# design_sch.net
KiCad netlist of a schematic drawn in EasyEDA
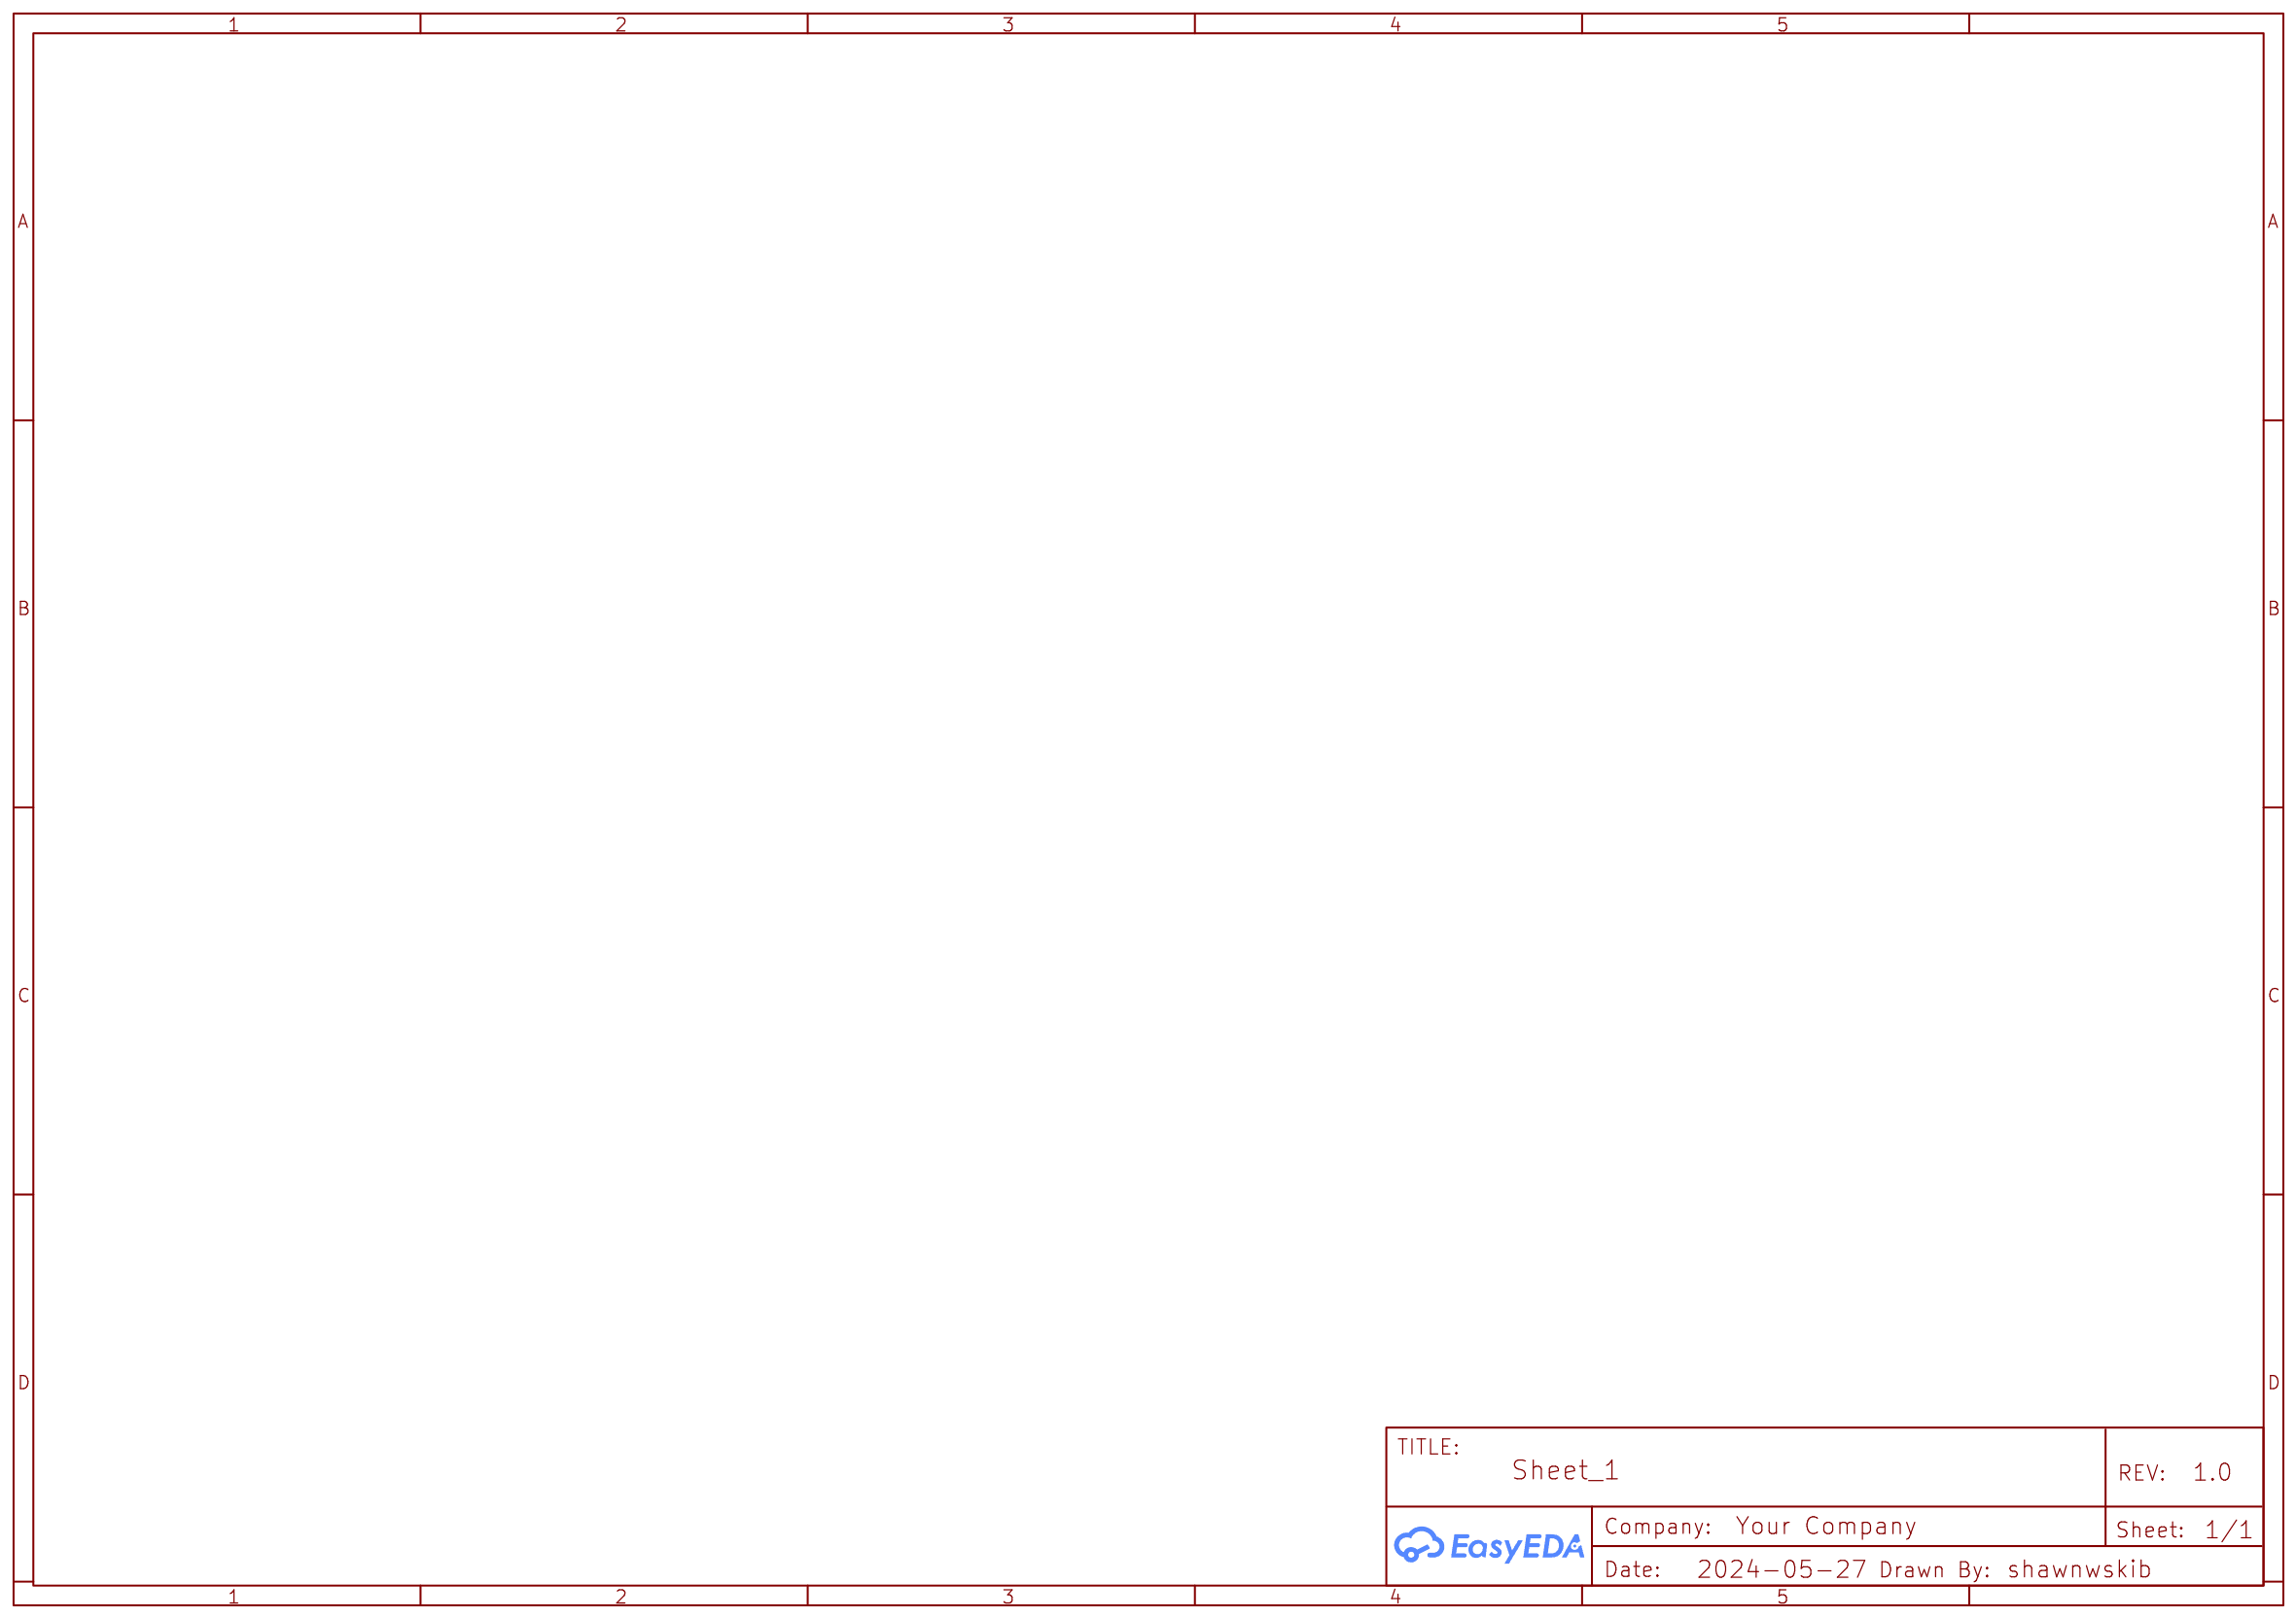
[diagram p0: Sheet_1]
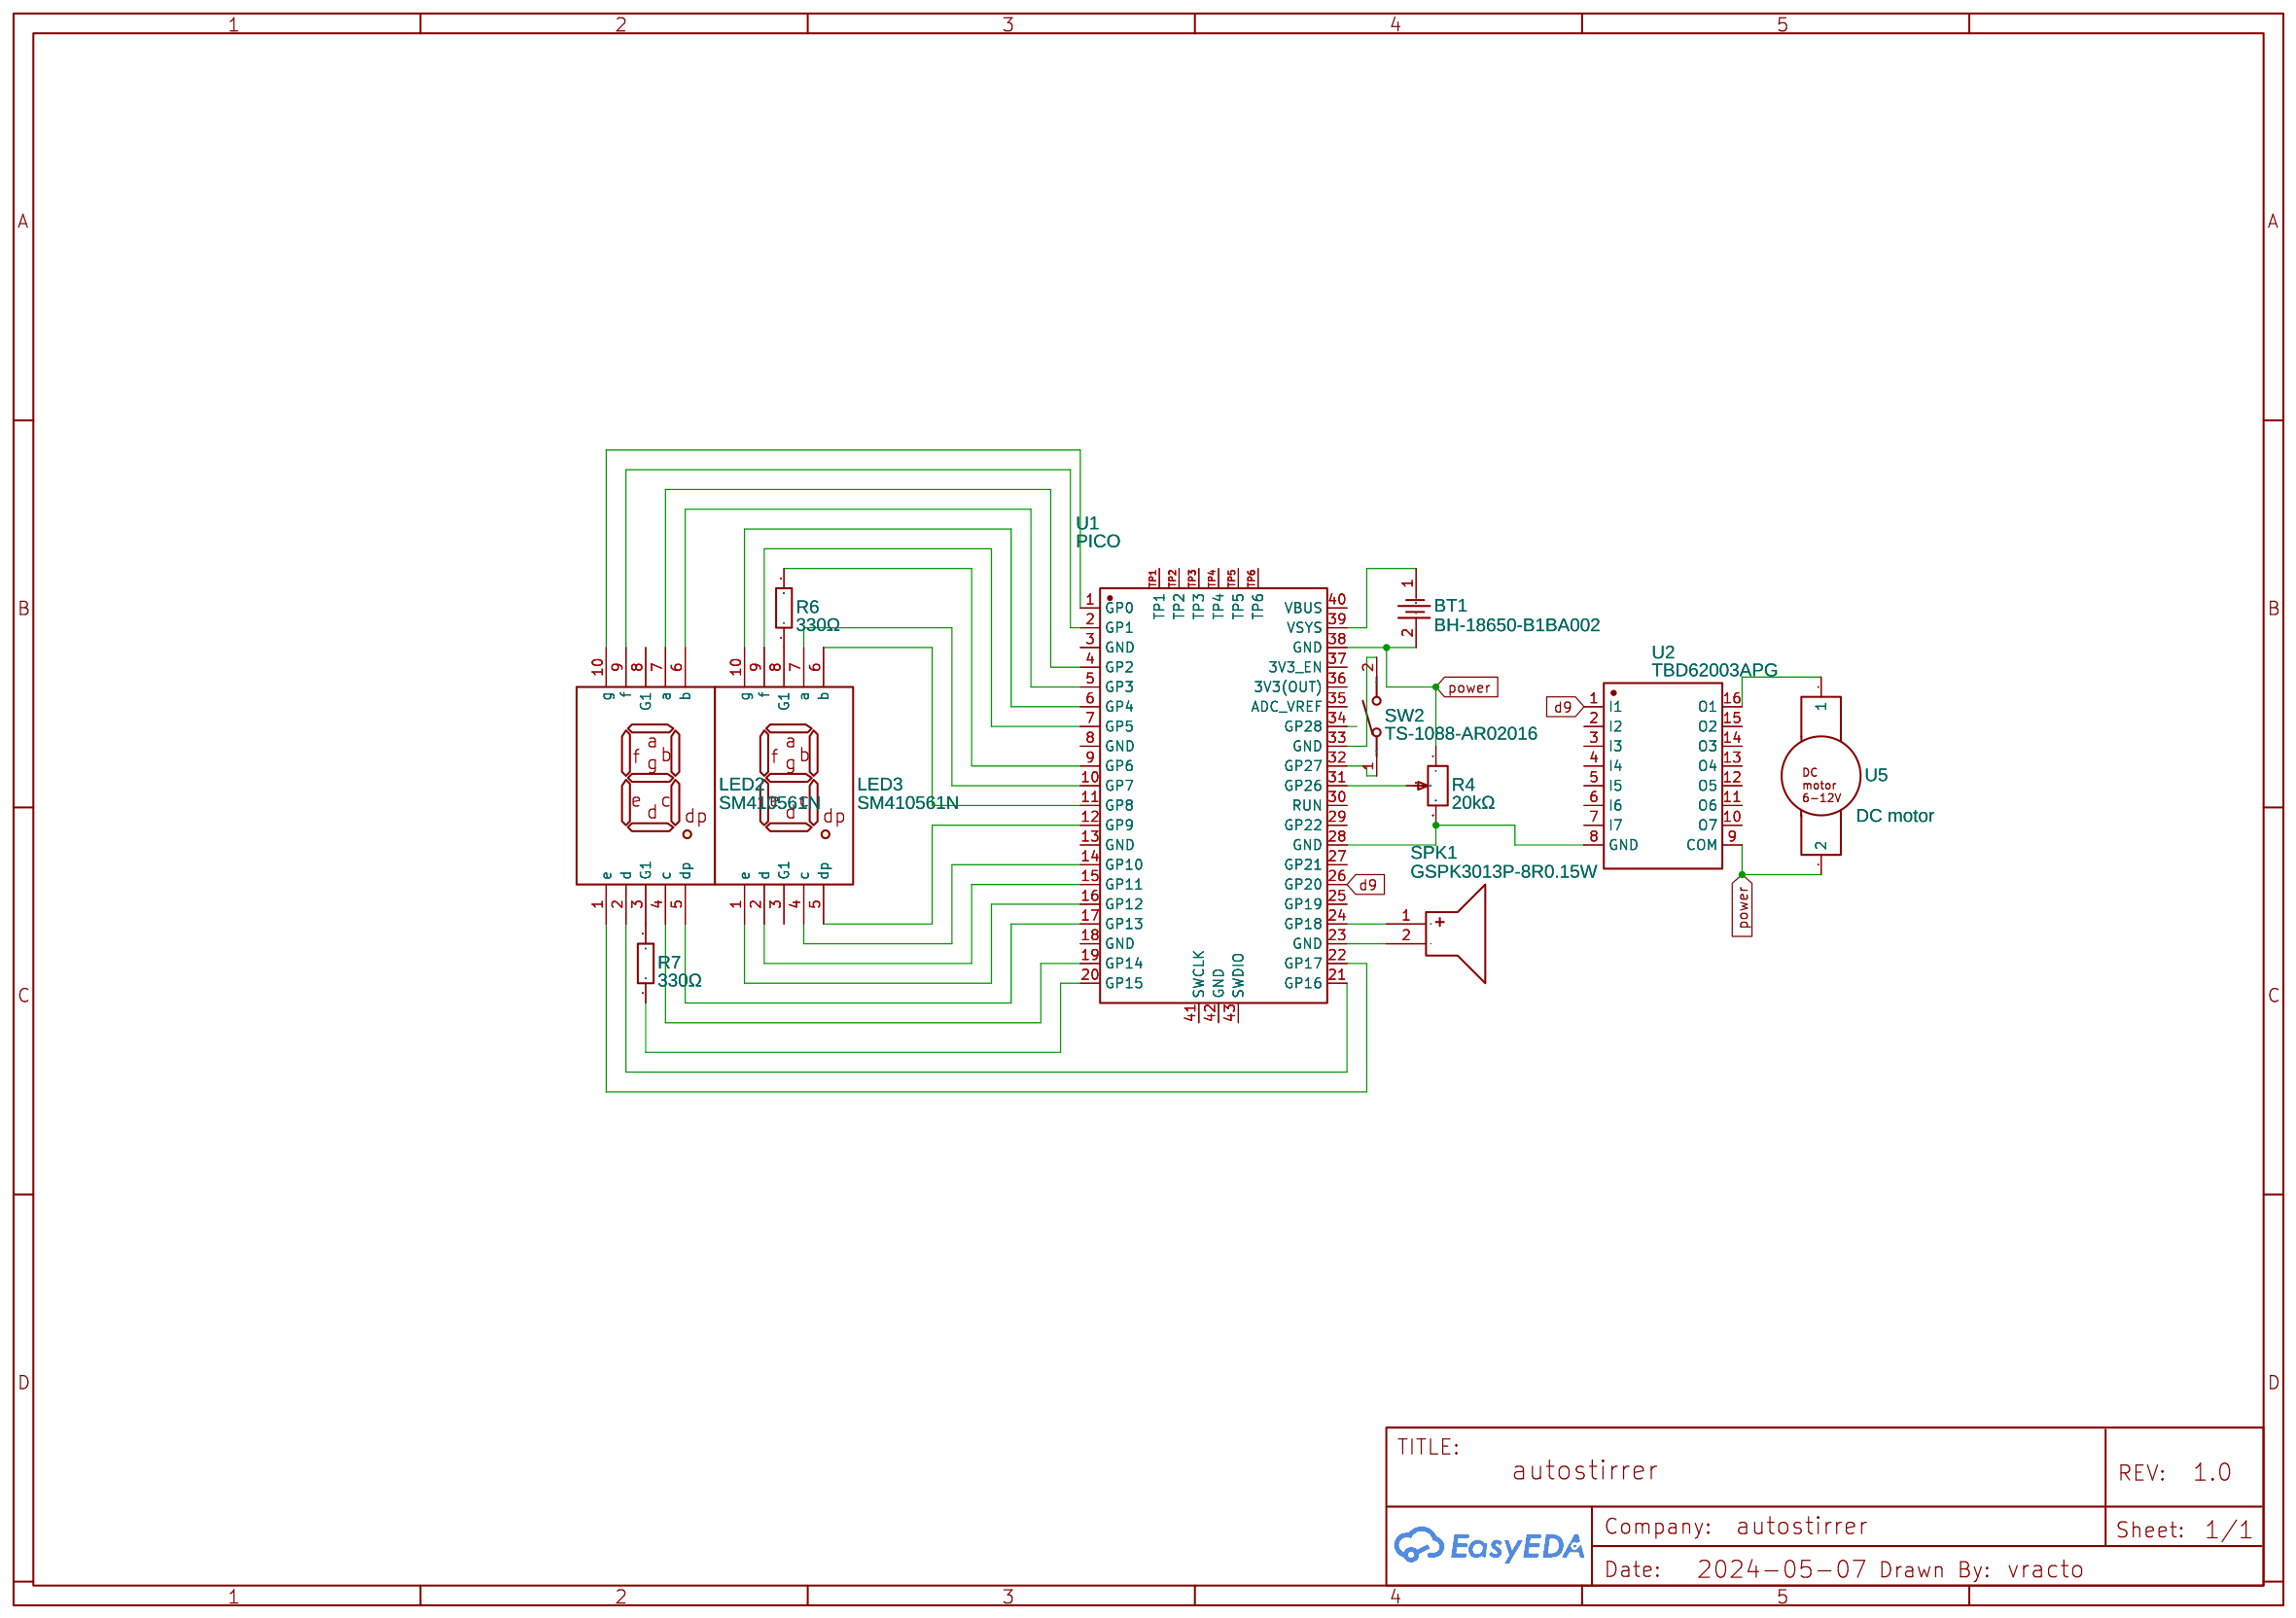
[diagram p1: v1.0.2]

(export (version "E")
  (design (tool "Eeschema 10.0.6"))
  (components
    (comp (ref "BT1")
      (value "BH-18650-B1BA002")
      (fields (field (name "Manufacturer") "MYOUNG(美阳)"))
      (libsource (lib "") (part "BH-18650-B1BA002"))
    )
    (comp (ref "LED2")
      (value "SM410561N")
      (fields (field (name "Manufacturer") "ARKLED(方舟)"))
      (libsource (lib "") (part "SM410561N"))
    )
    (comp (ref "LED3")
      (value "SM410561N")
      (fields (field (name "Manufacturer") "ARKLED(方舟)"))
      (libsource (lib "") (part "SM410561N"))
    )
    (comp (ref "R4")
      (value "20kΩ")
      (fields (field (name "Manufacturer Part") "3296W-1-203LF") (field (name "Manufacturer") "BOURNS"))
      (libsource (lib "") (part "3296W-1-203LF"))
    )
    (comp (ref "R6")
      (value "330Ω")
      (fields (field (name "Manufacturer Part") "MFR-25FTE52-330R") (field (name "Manufacturer") "YAGEO(国巨)"))
      (libsource (lib "") (part "MFR-25FTE52-330R"))
    )
    (comp (ref "R7")
      (value "330Ω")
      (fields (field (name "Manufacturer Part") "MFR-25FTE52-330R") (field (name "Manufacturer") "YAGEO(国巨)"))
      (libsource (lib "") (part "MFR-25FTE52-330R"))
    )
    (comp (ref "SPK1")
      (value "GSPK3013P-8R0.15W")
      (fields (field (name "Manufacturer") "INGHAi(赢海)"))
      (libsource (lib "") (part "GSPK3013P-8R0.15W"))
    )
    (comp (ref "SW2")
      (value "TS-1088-AR02016")
      (fields (field (name "Manufacturer") "XUNPU(讯普)"))
      (libsource (lib "") (part "TS-1088-AR02016"))
    )
    (comp (ref "U1")
      (value "PICO")
      (fields (field (name "Manufacturer") "Raspberry Pi(树莓派)"))
      (libsource (lib "") (part "PICO"))
    )
    (comp (ref "U2")
      (value "TBD62003APG")
      (fields
        (field (name "Manufacturer Part") "TBD62003APG(Z,HZ)")
        (field (name "Manufacturer") "TOSHIBA(东芝)")
      )
      (libsource (lib "") (part "TBD62003APG"))
    )
    (comp (ref "U5")
      (value "DC motor")
      (fields (field (name "Manufacturer Part") "?"))
      (libsource (lib "") (part "Unknown_915_-420"))
    )
  )
  (nets
    (net (code "1") (name "Net-(LED2-G1-Pad3)") (class "Default")
      (node (ref "LED2") (pin "3") (pinfunction "G1_3") (pintype "input"))
      (node (ref "R7") (pin "2") (pinfunction "2_2") (pintype "input"))
    )
    (net (code "2") (name "Net-(LED2-a)") (class "Default")
      (node (ref "LED2") (pin "7") (pinfunction "a_7") (pintype "input"))
      (node (ref "U1") (pin "4") (pinfunction "GP2_4") (pintype "unspecified"))
    )
    (net (code "3") (name "Net-(LED2-b)") (class "Default")
      (node (ref "LED2") (pin "6") (pinfunction "b_6") (pintype "input"))
      (node (ref "U1") (pin "5") (pinfunction "GP3_5") (pintype "unspecified"))
    )
    (net (code "4") (name "Net-(LED2-c)") (class "Default")
      (node (ref "LED2") (pin "4") (pinfunction "c_4") (pintype "input"))
      (node (ref "U1") (pin "19") (pinfunction "GP14_19") (pintype "unspecified"))
    )
    (net (code "5") (name "Net-(LED2-d)") (class "Default")
      (node (ref "LED2") (pin "2") (pinfunction "d_2") (pintype "input"))
      (node (ref "U1") (pin "21") (pinfunction "GP16_21") (pintype "unspecified"))
    )
    (net (code "6") (name "Net-(LED2-dp)") (class "Default")
      (node (ref "LED2") (pin "5") (pinfunction "dp_5") (pintype "input"))
      (node (ref "U1") (pin "17") (pinfunction "GP13_17") (pintype "unspecified"))
    )
    (net (code "7") (name "Net-(LED2-e)") (class "Default")
      (node (ref "LED2") (pin "1") (pinfunction "e_1") (pintype "input"))
      (node (ref "U1") (pin "22") (pinfunction "GP17_22") (pintype "unspecified"))
    )
    (net (code "8") (name "Net-(LED2-f)") (class "Default")
      (node (ref "LED2") (pin "9") (pinfunction "f_9") (pintype "input"))
      (node (ref "U1") (pin "2") (pinfunction "GP1_2") (pintype "unspecified"))
    )
    (net (code "9") (name "Net-(LED2-g)") (class "Default")
      (node (ref "LED2") (pin "10") (pinfunction "g_10") (pintype "input"))
      (node (ref "U1") (pin "1") (pinfunction "GP0_1") (pintype "unspecified"))
    )
    (net (code "10") (name "Net-(LED3-G1-Pad8)") (class "Default")
      (node (ref "LED3") (pin "8") (pinfunction "G1_8") (pintype "input"))
      (node (ref "R6") (pin "1") (pinfunction "1_1") (pintype "input"))
    )
    (net (code "11") (name "Net-(LED3-a)") (class "Default")
      (node (ref "LED3") (pin "7") (pinfunction "a_7") (pintype "input"))
      (node (ref "U1") (pin "10") (pinfunction "GP7_10") (pintype "unspecified"))
    )
    (net (code "12") (name "Net-(LED3-b)") (class "Default")
      (node (ref "LED3") (pin "6") (pinfunction "b_6") (pintype "input"))
      (node (ref "U1") (pin "11") (pinfunction "GP8_11") (pintype "unspecified"))
    )
    (net (code "13") (name "Net-(LED3-c)") (class "Default")
      (node (ref "LED3") (pin "4") (pinfunction "c_4") (pintype "input"))
      (node (ref "U1") (pin "14") (pinfunction "GP10_14") (pintype "unspecified"))
    )
    (net (code "14") (name "Net-(LED3-d)") (class "Default")
      (node (ref "LED3") (pin "2") (pinfunction "d_2") (pintype "input"))
      (node (ref "U1") (pin "15") (pinfunction "GP11_15") (pintype "unspecified"))
    )
    (net (code "15") (name "Net-(LED3-dp)") (class "Default")
      (node (ref "LED3") (pin "5") (pinfunction "dp_5") (pintype "input"))
      (node (ref "U1") (pin "12") (pinfunction "GP9_12") (pintype "unspecified"))
    )
    (net (code "16") (name "Net-(LED3-e)") (class "Default")
      (node (ref "LED3") (pin "1") (pinfunction "e_1") (pintype "input"))
      (node (ref "U1") (pin "16") (pinfunction "GP12_16") (pintype "unspecified"))
    )
    (net (code "17") (name "Net-(LED3-f)") (class "Default")
      (node (ref "LED3") (pin "9") (pinfunction "f_9") (pintype "input"))
      (node (ref "U1") (pin "7") (pinfunction "GP5_7") (pintype "unspecified"))
    )
    (net (code "18") (name "Net-(LED3-g)") (class "Default")
      (node (ref "LED3") (pin "10") (pinfunction "g_10") (pintype "input"))
      (node (ref "U1") (pin "6") (pinfunction "GP4_6") (pintype "unspecified"))
    )
    (net (code "19") (name "Net-(SPK1-+)") (class "Default")
      (node (ref "SPK1") (pin "1") (pinfunction "+_1") (pintype "unspecified"))
      (node (ref "U1") (pin "24") (pinfunction "GP18_24") (pintype "unspecified"))
    )
    (net (code "20") (name "Net-(SPK1--)") (class "Default")
      (node (ref "SPK1") (pin "2") (pinfunction "-_2") (pintype "unspecified"))
      (node (ref "U1") (pin "23") (pinfunction "GND_23") (pintype "unspecified"))
    )
    (net (code "21") (name "Net-(SW2-Pad2)") (class "Default")
      (node (ref "SW2") (pin "2") (pinfunction "2_2") (pintype "unspecified"))
      (node (ref "U1") (pin "33") (pinfunction "GND_33") (pintype "unspecified"))
    )
    (net (code "22") (name "Net-(U1-GP6)") (class "Default")
      (node (ref "R6") (pin "2") (pinfunction "2_2") (pintype "input"))
      (node (ref "U1") (pin "9") (pinfunction "GP6_9") (pintype "unspecified"))
    )
    (net (code "23") (name "Net-(U1-GP15)") (class "Default")
      (node (ref "R7") (pin "1") (pinfunction "1_1") (pintype "input"))
      (node (ref "U1") (pin "20") (pinfunction "GP15_20") (pintype "unspecified"))
    )
    (net (code "24") (name "Net-(U1-GP26)") (class "Default")
      (node (ref "R4") (pin "2") (pinfunction "2_2") (pintype "input"))
      (node (ref "U1") (pin "31") (pinfunction "GP26_31") (pintype "unspecified"))
    )
    (net (code "25") (name "Net-(U1-GP27)") (class "Default")
      (node (ref "SW2") (pin "1") (pinfunction "1_1") (pintype "unspecified"))
      (node (ref "U1") (pin "32") (pinfunction "GP27_32") (pintype "unspecified"))
    )
    (net (code "26") (name "Net-(U1-VSYS)") (class "Default")
      (node (ref "BT1") (pin "1") (pinfunction "1_1") (pintype "input"))
      (node (ref "U1") (pin "39") (pinfunction "VSYS_39") (pintype "unspecified"))
    )
    (net (code "27") (name "Net-(U2-GND)") (class "Default")
      (node (ref "R4") (pin "3") (pinfunction "3_3") (pintype "input"))
      (node (ref "U1") (pin "28") (pinfunction "GND_28") (pintype "unspecified"))
      (node (ref "U2") (pin "8") (pinfunction "GND_8") (pintype "unspecified"))
    )
    (net (code "28") (name "Net-(U2-O1)") (class "Default")
      (node (ref "U2") (pin "16") (pinfunction "O1_16") (pintype "unspecified"))
      (node (ref "U5") (pin "1") (pinfunction "1_1") (pintype "unspecified"))
    )
    (net (code "29") (name "d9") (class "Default")
      (node (ref "U1") (pin "26") (pinfunction "GP20_26") (pintype "unspecified"))
      (node (ref "U2") (pin "1") (pinfunction "I1_1") (pintype "unspecified"))
    )
    (net (code "30") (name "power") (class "Default")
      (node (ref "BT1") (pin "2") (pinfunction "2_2") (pintype "input"))
      (node (ref "R4") (pin "1") (pinfunction "1_1") (pintype "input"))
      (node (ref "U1") (pin "38") (pinfunction "GND_38") (pintype "unspecified"))
      (node (ref "U2") (pin "9") (pinfunction "COM_9") (pintype "unspecified"))
      (node (ref "U5") (pin "2") (pinfunction "2_2") (pintype "unspecified"))
    )
    (net (code "31") (name "unconnected-(LED2-G1-Pad8)") (class "Default")
      (node (ref "LED2") (pin "8") (pinfunction "G1_8") (pintype "input"))
    )
    (net (code "32") (name "unconnected-(LED3-G1-Pad3)") (class "Default")
      (node (ref "LED3") (pin "3") (pinfunction "G1_3") (pintype "input"))
    )
    (net (code "33") (name "unconnected-(U1-3V3(OUT)-Pad36)") (class "Default")
      (node (ref "U1") (pin "36") (pinfunction "3V3(OUT)_36") (pintype "unspecified"))
    )
    (net (code "34") (name "unconnected-(U1-3V3_EN-Pad37)") (class "Default")
      (node (ref "U1") (pin "37") (pinfunction "3V3_EN_37") (pintype "unspecified"))
    )
    (net (code "35") (name "unconnected-(U1-ADC_VREF-Pad35)") (class "Default")
      (node (ref "U1") (pin "35") (pinfunction "ADC_VREF_35") (pintype "unspecified"))
    )
    (net (code "36") (name "unconnected-(U1-GND-Pad3)") (class "Default")
      (node (ref "U1") (pin "3") (pinfunction "GND_3") (pintype "unspecified"))
    )
    (net (code "37") (name "unconnected-(U1-GND-Pad8)") (class "Default")
      (node (ref "U1") (pin "8") (pinfunction "GND_8") (pintype "unspecified"))
    )
    (net (code "38") (name "unconnected-(U1-GND-Pad13)") (class "Default")
      (node (ref "U1") (pin "13") (pinfunction "GND_13") (pintype "unspecified"))
    )
    (net (code "39") (name "unconnected-(U1-GND-Pad18)") (class "Default")
      (node (ref "U1") (pin "18") (pinfunction "GND_18") (pintype "unspecified"))
    )
    (net (code "40") (name "unconnected-(U1-GND-Pad42)") (class "Default")
      (node (ref "U1") (pin "42") (pinfunction "GND_42") (pintype "unspecified"))
    )
    (net (code "41") (name "unconnected-(U1-GP19-Pad25)") (class "Default")
      (node (ref "U1") (pin "25") (pinfunction "GP19_25") (pintype "unspecified"))
    )
    (net (code "42") (name "unconnected-(U1-GP21-Pad27)") (class "Default")
      (node (ref "U1") (pin "27") (pinfunction "GP21_27") (pintype "unspecified"))
    )
    (net (code "43") (name "unconnected-(U1-GP22-Pad29)") (class "Default")
      (node (ref "U1") (pin "29") (pinfunction "GP22_29") (pintype "unspecified"))
    )
    (net (code "44") (name "unconnected-(U1-GP28-Pad34)") (class "Default")
      (node (ref "U1") (pin "34") (pinfunction "GP28_34") (pintype "unspecified"))
    )
    (net (code "45") (name "unconnected-(U1-PadTP1)") (class "Default")
      (node (ref "U1") (pin "TP1") (pinfunction "TP1_TP1") (pintype "unspecified"))
    )
    (net (code "46") (name "unconnected-(U1-PadTP2)") (class "Default")
      (node (ref "U1") (pin "TP2") (pinfunction "TP2_TP2") (pintype "unspecified"))
    )
    (net (code "47") (name "unconnected-(U1-PadTP3)") (class "Default")
      (node (ref "U1") (pin "TP3") (pinfunction "TP3_TP3") (pintype "unspecified"))
    )
    (net (code "48") (name "unconnected-(U1-PadTP4)") (class "Default")
      (node (ref "U1") (pin "TP4") (pinfunction "TP4_TP4") (pintype "unspecified"))
    )
    (net (code "49") (name "unconnected-(U1-PadTP5)") (class "Default")
      (node (ref "U1") (pin "TP5") (pinfunction "TP5_TP5") (pintype "unspecified"))
    )
    (net (code "50") (name "unconnected-(U1-PadTP6)") (class "Default")
      (node (ref "U1") (pin "TP6") (pinfunction "TP6_TP6") (pintype "unspecified"))
    )
    (net (code "51") (name "unconnected-(U1-RUN-Pad30)") (class "Default")
      (node (ref "U1") (pin "30") (pinfunction "RUN_30") (pintype "unspecified"))
    )
    (net (code "52") (name "unconnected-(U1-SWCLK-Pad41)") (class "Default")
      (node (ref "U1") (pin "41") (pinfunction "SWCLK_41") (pintype "unspecified"))
    )
    (net (code "53") (name "unconnected-(U1-SWDIO-Pad43)") (class "Default")
      (node (ref "U1") (pin "43") (pinfunction "SWDIO_43") (pintype "unspecified"))
    )
    (net (code "54") (name "unconnected-(U1-VBUS-Pad40)") (class "Default")
      (node (ref "U1") (pin "40") (pinfunction "VBUS_40") (pintype "unspecified"))
    )
    (net (code "55") (name "unconnected-(U2-I2-Pad2)") (class "Default")
      (node (ref "U2") (pin "2") (pinfunction "I2_2") (pintype "unspecified"))
    )
    (net (code "56") (name "unconnected-(U2-I3-Pad3)") (class "Default")
      (node (ref "U2") (pin "3") (pinfunction "I3_3") (pintype "unspecified"))
    )
    (net (code "57") (name "unconnected-(U2-I4-Pad4)") (class "Default")
      (node (ref "U2") (pin "4") (pinfunction "I4_4") (pintype "unspecified"))
    )
    (net (code "58") (name "unconnected-(U2-I5-Pad5)") (class "Default")
      (node (ref "U2") (pin "5") (pinfunction "I5_5") (pintype "unspecified"))
    )
    (net (code "59") (name "unconnected-(U2-I6-Pad6)") (class "Default")
      (node (ref "U2") (pin "6") (pinfunction "I6_6") (pintype "unspecified"))
    )
    (net (code "60") (name "unconnected-(U2-I7-Pad7)") (class "Default")
      (node (ref "U2") (pin "7") (pinfunction "I7_7") (pintype "unspecified"))
    )
    (net (code "61") (name "unconnected-(U2-O2-Pad15)") (class "Default")
      (node (ref "U2") (pin "15") (pinfunction "O2_15") (pintype "unspecified"))
    )
    (net (code "62") (name "unconnected-(U2-O3-Pad14)") (class "Default")
      (node (ref "U2") (pin "14") (pinfunction "O3_14") (pintype "unspecified"))
    )
    (net (code "63") (name "unconnected-(U2-O4-Pad13)") (class "Default")
      (node (ref "U2") (pin "13") (pinfunction "O4_13") (pintype "unspecified"))
    )
    (net (code "64") (name "unconnected-(U2-O5-Pad12)") (class "Default")
      (node (ref "U2") (pin "12") (pinfunction "O5_12") (pintype "unspecified"))
    )
    (net (code "65") (name "unconnected-(U2-O6-Pad11)") (class "Default")
      (node (ref "U2") (pin "11") (pinfunction "O6_11") (pintype "unspecified"))
    )
    (net (code "66") (name "unconnected-(U2-O7-Pad10)") (class "Default")
      (node (ref "U2") (pin "10") (pinfunction "O7_10") (pintype "unspecified"))
    )
  )
)
